# 1A20J10_1A21J4_A.net
KiCad netlist of a schematic drawn in Altium Designer
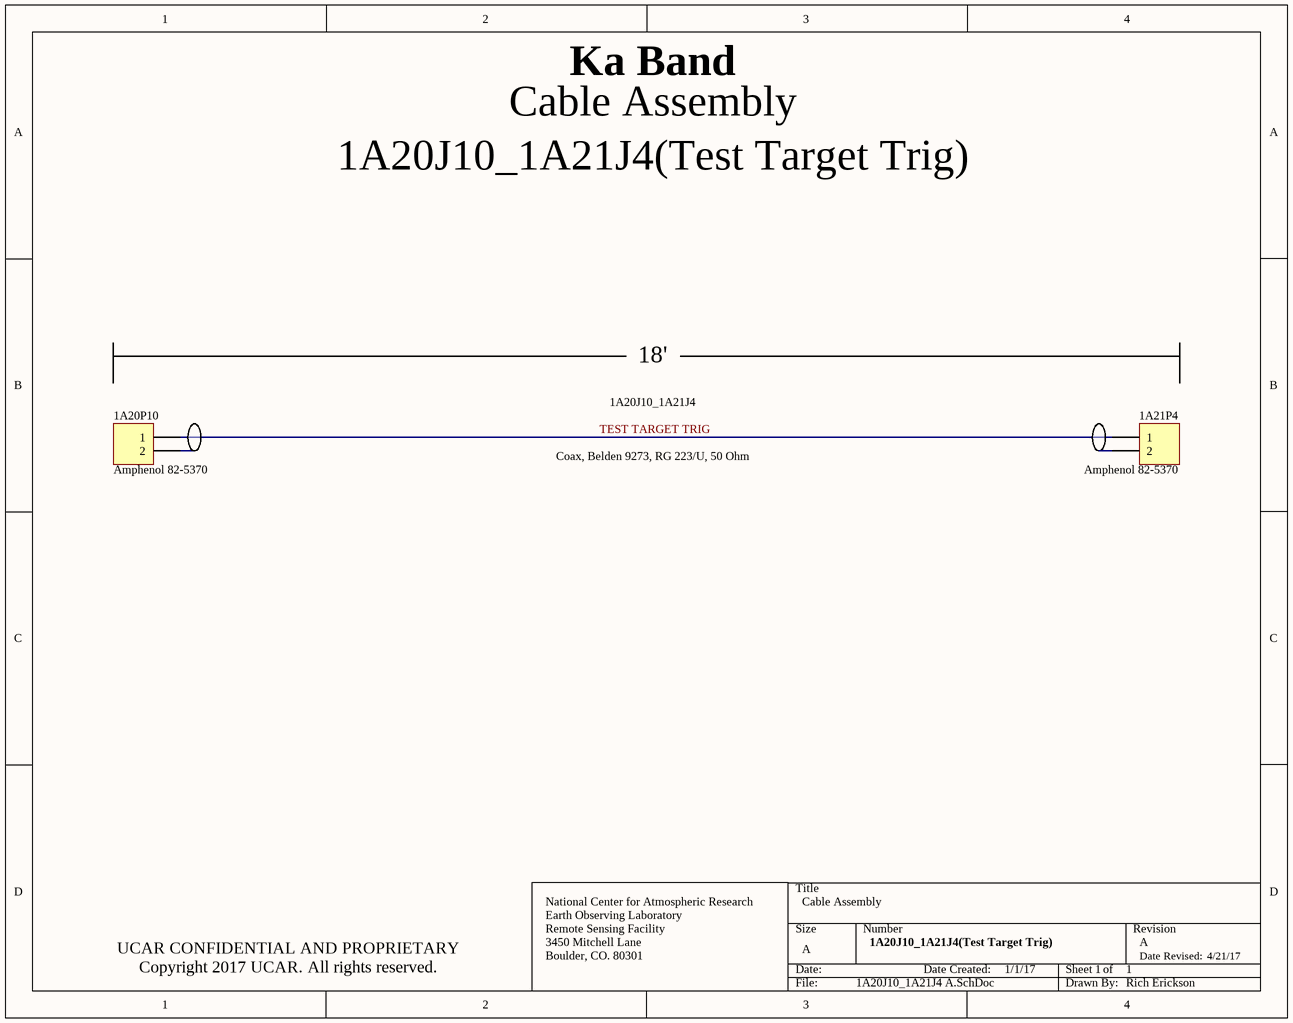
[diagram p0: 1A20J10_1A21J4 A.SchDoc]

(export (version "E")
  (design (tool "Eeschema 10.0.6"))
  (components
    (comp (ref "1A20P10")
      (value "Amphenol 82-5370")
      (footprint "HDR1X2")
      (description "Header, 2-Pin")
      (fields (field (name "PUBLISHER") "Altium Limited"))
      (libsource (lib "Miscellaneous Connectors") (part "Header 2"))
    )
    (comp (ref "1A21P4")
      (value "Amphenol 82-5370")
      (footprint "HDR1X2")
      (description "Header, 2-Pin")
      (fields (field (name "PUBLISHER") "Altium Limited"))
      (libsource (lib "") (part "Header 2_1"))
    )
  )
  (nets
    (net (code "1") (name "/TEST TARGET TRIG") (class "Default")
      (node (ref "1A20P10") (pin "1") (pinfunction "1_1") (pintype "passive"))
      (node (ref "1A21P4") (pin "1") (pinfunction "1_1") (pintype "passive"))
    )
    (net (code "2") (name "unconnected-(1A20P10-Pad2)") (class "Default")
      (node (ref "1A20P10") (pin "2") (pinfunction "2_2") (pintype "passive"))
    )
    (net (code "3") (name "unconnected-(1A21P4-Pad2)") (class "Default")
      (node (ref "1A21P4") (pin "2") (pinfunction "2_2") (pintype "passive"))
    )
  )
)
